# WaterPumpDriver.net
KiCad netlist of a schematic drawn in EasyEDA Pro
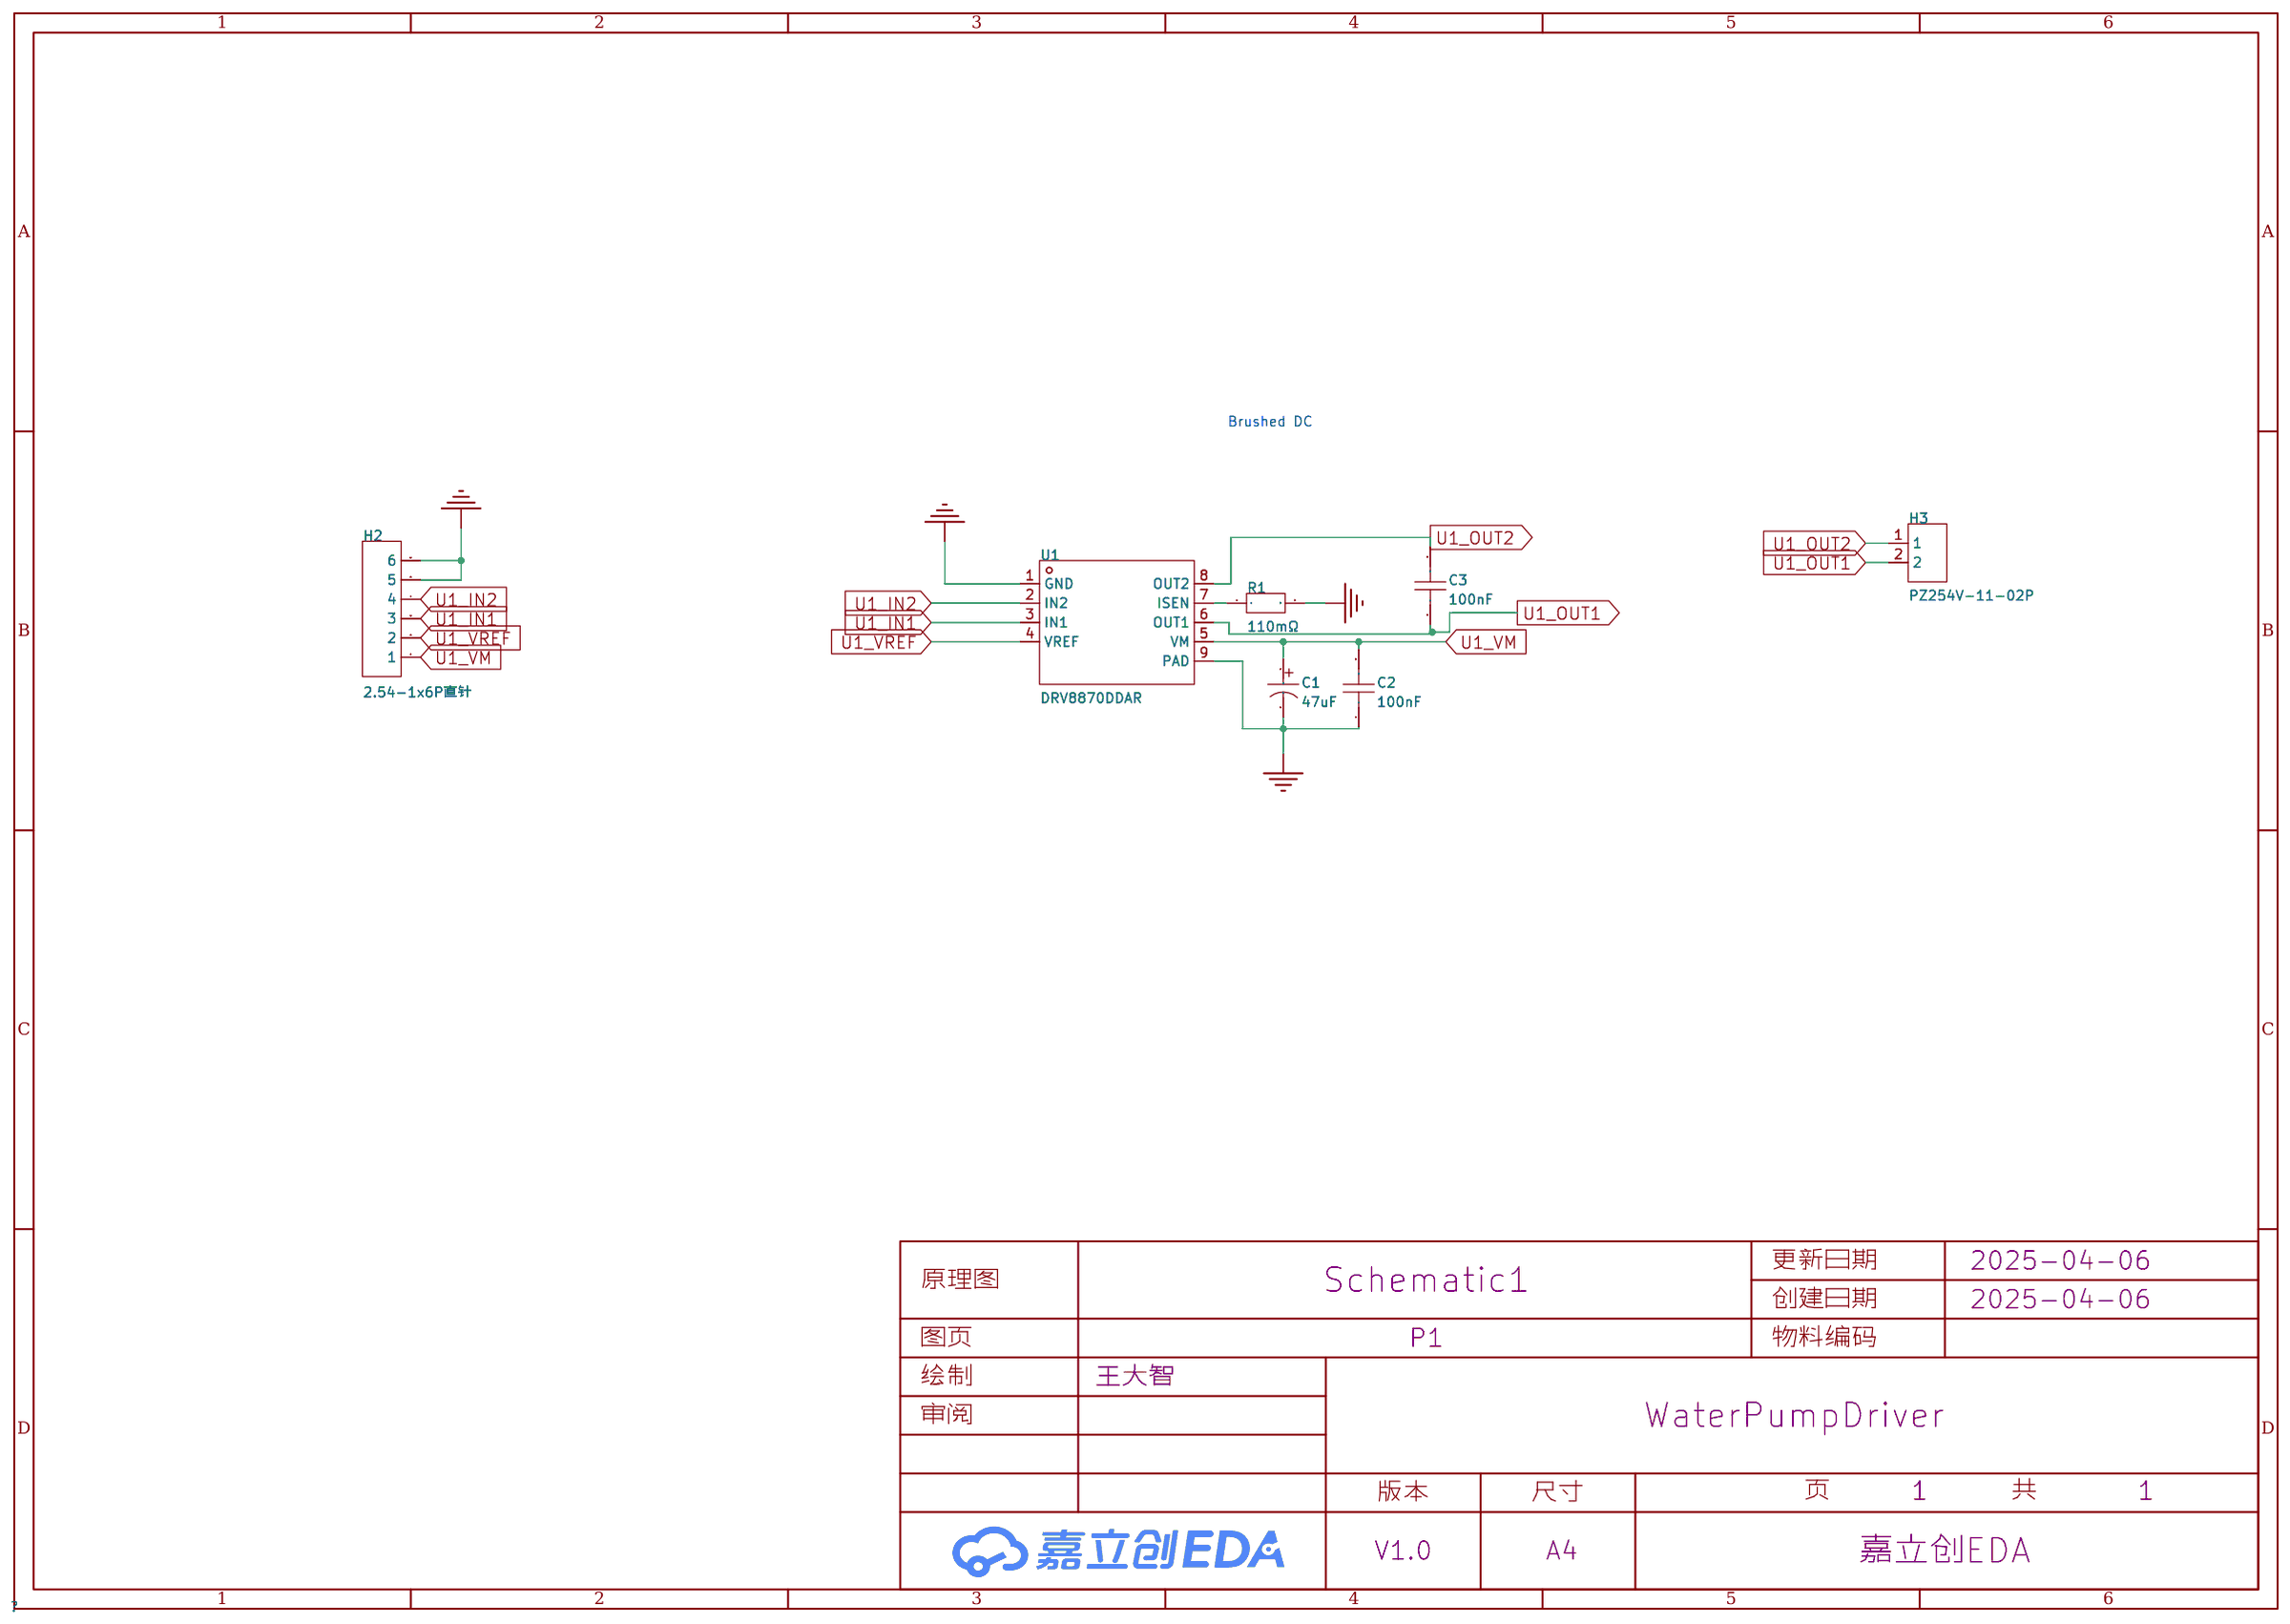
[diagram p0: schematic sheet]

(export (version "E")
  (design (tool "Eeschema 10.0.6"))
  (components
    (comp (ref "C1")
      (value "47uF")
      (footprint "easyedapro:CAP-TH_BD6.3-P2.50-D1.0-FD")
      (description "容值:47uF;精度:±20%;额定电压:50V;")
      (fields
        (field (name "Manufacturer Part") "KM476M050E11RR0VH2FP0")
        (field (name "Manufacturer") "CX(承兴)")
      )
      (libsource (lib "easyedapro") (part "47uF 50V 6.3*11_C45101"))
    )
    (comp (ref "C2")
      (value "100nF")
      (footprint "easyedapro:C0603")
      (description "容值:100nF;精度:±10%;额定电压:50V;温度系数:X7R;")
      (fields
        (field (name "Manufacturer Part") "CGA0603X7R104K500JT")
        (field (name "Manufacturer") "HRE(芯声)")
      )
      (libsource (lib "easyedapro") (part "CGA0603X7R104K500JT"))
    )
    (comp (ref "C3")
      (value "100nF")
      (footprint "easyedapro:C0603")
      (description "容值:100nF;精度:±10%;额定电压:50V;温度系数:X7R;")
      (fields
        (field (name "Manufacturer Part") "CGA0603X7R104K500JT")
        (field (name "Manufacturer") "HRE(芯声)")
      )
      (libsource (lib "easyedapro") (part "CGA0603X7R104K500JT"))
    )
    (comp (ref "H2")
      (value "2.54-1x6P直针")
      (footprint "easyedapro:HDR-TH_6P-P2.54-V-M-1")
      (fields (field (name "Manufacturer") "BOOMELE(博穆精密)"))
      (libsource (lib "easyedapro") (part "Header-Male-2.54_1x6"))
    )
    (comp (ref "H3")
      (value "PZ254V-11-02P")
      (footprint "easyedapro:HDR-TH_2P-P2.54-V-M")
      (fields (field (name "Manufacturer") "XFCN(兴飞)"))
      (libsource (lib "easyedapro") (part "PZ254V-11-02P"))
    )
    (comp (ref "R1")
      (value "110mΩ")
      (footprint "easyedapro:R1206")
      (description "电阻类型:厚膜电阻;阻值:110mΩ;精度:±1%;功率:250mW;最大工作电压:500V;温度系数:±600ppm/°C;")
      (fields (field (name "Manufacturer Part") "FRL1206FR110TS") (field (name "Manufacturer") "FOJAN(富捷)"))
      (libsource (lib "easyedapro") (part "FRL1206FR110TS"))
    )
    (comp (ref "U1")
      (value "DRV8870DDAR")
      (footprint "easyedapro:HSOP-8_L5.0-W4.0-P1.27-LS6.2-BL-EP")
      (description "DRV8870 具有电流调节功能的 50V、3.6A、H 桥电机驱动器")
      (fields (field (name "Manufacturer") "TI(德州仪器)"))
      (libsource (lib "easyedapro") (part "DRV8870DDAR"))
    )
  )
  (nets
    (net (code "1") (name "GND") (class "Default")
      (node (ref "C1") (pin "2") (pinfunction "2_2") (pintype "input"))
      (node (ref "C2") (pin "1") (pinfunction "1_1") (pintype "unspecified"))
      (node (ref "H2") (pin "5") (pinfunction "5_5") (pintype "input"))
      (node (ref "H2") (pin "6") (pinfunction "6_6") (pintype "input"))
      (node (ref "R1") (pin "2") (pinfunction "2_2") (pintype "unspecified"))
      (node (ref "U1") (pin "1") (pinfunction "GND_1") (pintype "unspecified"))
      (node (ref "U1") (pin "9") (pinfunction "PAD_9") (pintype "unspecified"))
    )
    (net (code "2") (name "Net-(U1-ISEN)") (class "Default")
      (node (ref "R1") (pin "1") (pinfunction "1_1") (pintype "unspecified"))
      (node (ref "U1") (pin "7") (pinfunction "ISEN_7") (pintype "unspecified"))
    )
    (net (code "3") (name "U1_IN1") (class "Default")
      (node (ref "H2") (pin "3") (pinfunction "3_3") (pintype "input"))
      (node (ref "U1") (pin "3") (pinfunction "IN1_3") (pintype "unspecified"))
    )
    (net (code "4") (name "U1_IN2") (class "Default")
      (node (ref "H2") (pin "4") (pinfunction "4_4") (pintype "input"))
      (node (ref "U1") (pin "2") (pinfunction "IN2_2") (pintype "unspecified"))
    )
    (net (code "5") (name "U1_OUT1") (class "Default")
      (node (ref "C3") (pin "1") (pinfunction "1_1") (pintype "unspecified"))
      (node (ref "H3") (pin "2") (pinfunction "2_2") (pintype "unspecified"))
      (node (ref "U1") (pin "6") (pinfunction "OUT1_6") (pintype "unspecified"))
    )
    (net (code "6") (name "U1_OUT2") (class "Default")
      (node (ref "C3") (pin "2") (pinfunction "2_2") (pintype "unspecified"))
      (node (ref "H3") (pin "1") (pinfunction "1_1") (pintype "unspecified"))
      (node (ref "U1") (pin "8") (pinfunction "OUT2_8") (pintype "unspecified"))
    )
    (net (code "7") (name "U1_VM") (class "Default")
      (node (ref "C1") (pin "1") (pinfunction "1_1") (pintype "input"))
      (node (ref "C2") (pin "2") (pinfunction "2_2") (pintype "unspecified"))
      (node (ref "H2") (pin "1") (pinfunction "1_1") (pintype "input"))
      (node (ref "U1") (pin "5") (pinfunction "VM_5") (pintype "unspecified"))
    )
    (net (code "8") (name "U1_VREF") (class "Default")
      (node (ref "H2") (pin "2") (pinfunction "2_2") (pintype "input"))
      (node (ref "U1") (pin "4") (pinfunction "VREF_4") (pintype "unspecified"))
    )
  )
)
